# nice_n_simple_3340_v3.net
KiCad netlist of a schematic drawn in EAGLE
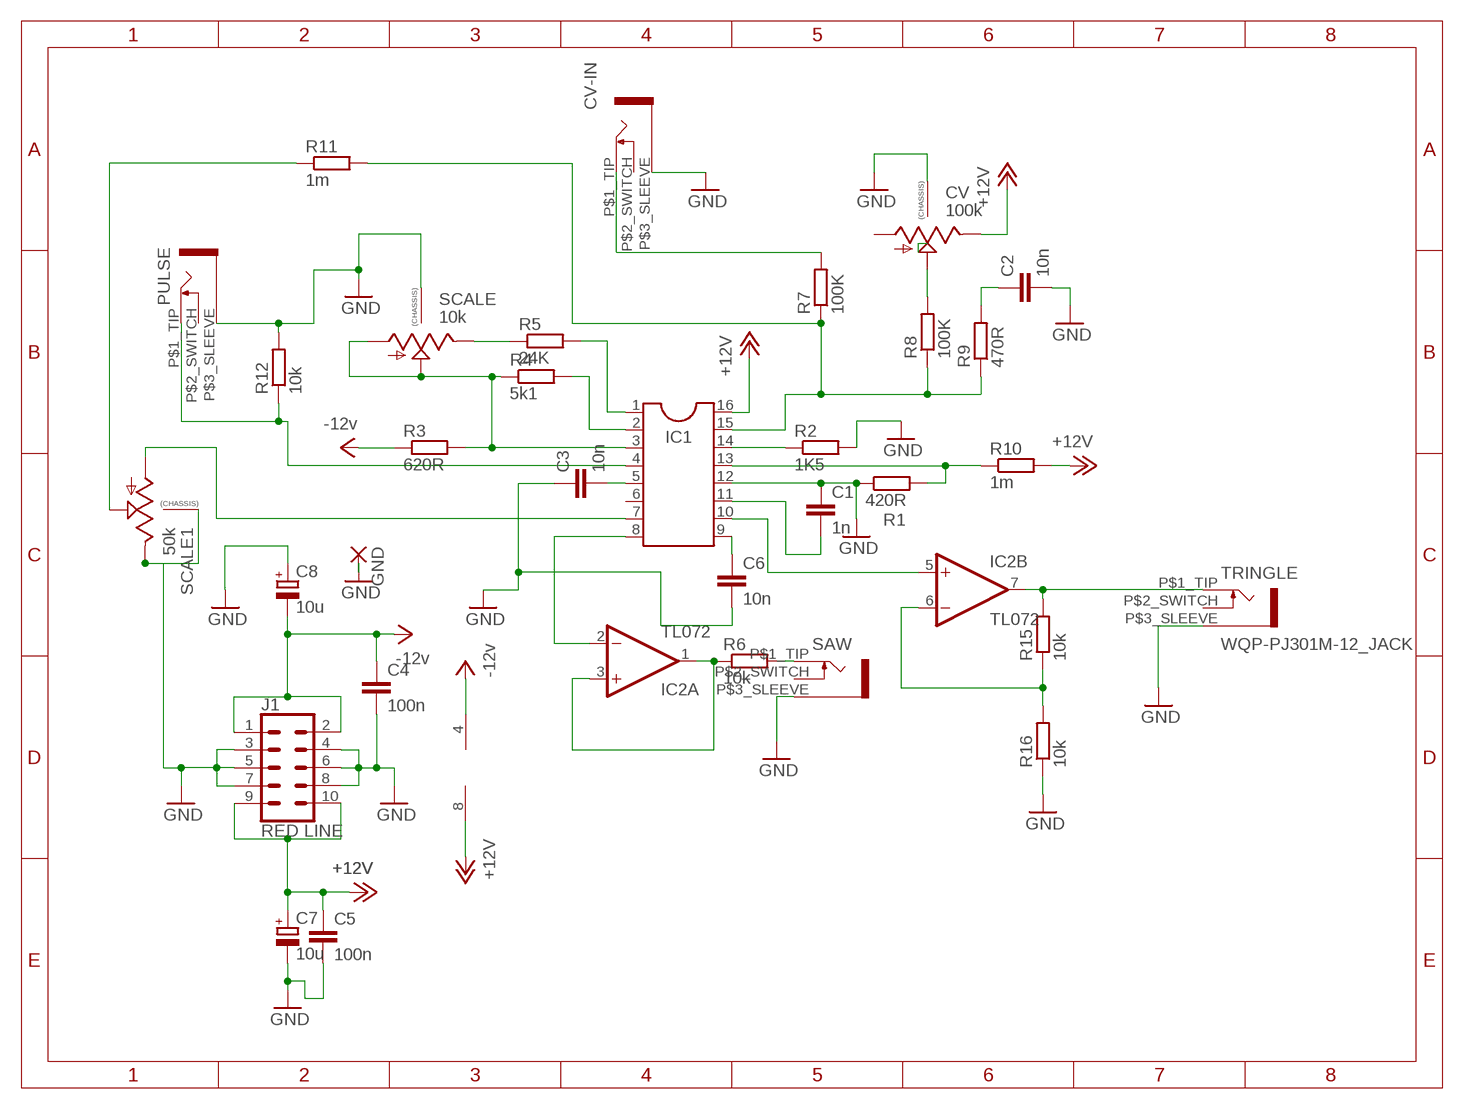
[diagram p0: schematic, sheet 1]

(export (version "E")
  (design (tool "Eeschema 10.0.6"))
  (components
    (comp (ref "C1")
      (value "1n")
      (footprint "eagle-import:C5B2.5")
      (libsource (lib "eagle-import") (part "C5/2.5"))
    )
    (comp (ref "C2")
      (value "10n")
      (footprint "eagle-import:C5B2.5")
      (libsource (lib "eagle-import") (part "C5/2.5"))
    )
    (comp (ref "C3")
      (value "10n")
      (footprint "eagle-import:C5B2.5")
      (libsource (lib "eagle-import") (part "C5/2.5"))
    )
    (comp (ref "C4")
      (value "100n")
      (footprint "eagle-import:C5B2.5")
      (libsource (lib "eagle-import") (part "C5/2.5"))
    )
    (comp (ref "C5")
      (value "100n")
      (footprint "eagle-import:C5B2.5")
      (libsource (lib "eagle-import") (part "C5/2.5"))
    )
    (comp (ref "C6")
      (value "10n")
      (footprint "eagle-import:C5B2.5")
      (libsource (lib "eagle-import") (part "C5/2.5"))
    )
    (comp (ref "C7")
      (value "10u")
      (footprint "eagle-import:E1,8-4")
      (libsource (lib "eagle-import") (part "CPOL-EUE1.8-4"))
    )
    (comp (ref "C8")
      (value "10u")
      (footprint "eagle-import:E1,8-4")
      (libsource (lib "eagle-import") (part "CPOL-EUE1.8-4"))
    )
    (comp (ref "CV")
      (value "100k")
      (footprint "eagle-import:9MM_SNAP-IN_POT")
      (libsource (lib "eagle-import") (part "9MM_SNAP-IN_POT_CHASSIS"))
    )
    (comp (ref "CV-IN")
      (value "WQP-PJ301M-12_JACK")
      (footprint "eagle-import:WQP-PJ301M-12_JACK")
      (libsource (lib "eagle-import") (part "WQP-PJ301M-12_JACK"))
    )
    (comp (ref "GND")
      (value "WIREPAD1,6/0,9")
      (footprint "eagle-import:1,6_0,9")
      (libsource (lib "eagle-import") (part "WIREPAD1,6/0,9"))
    )
    (comp (ref "IC1")
      (value "CEM3340")
      (footprint "eagle-import:SOCKET-16")
      (libsource (lib "eagle-import") (part "DIL16S"))
    )
    (comp (ref "IC2")
      (value "TL072")
      (footprint "eagle-import:DIL08")
      (libsource (lib "eagle-import") (part "TL072P"))
    )
    (comp (ref "J1")
      (value "RED LINE")
      (footprint "eagle-import:2X5-SHROUDED-NS")
      (libsource (lib "eagle-import") (part "CONN_05X2SHD-NS"))
    )
    (comp (ref "PULSE")
      (value "WQP-PJ301M-12_JACK")
      (footprint "eagle-import:WQP-PJ301M-12_JACK")
      (libsource (lib "eagle-import") (part "WQP-PJ301M-12_JACK"))
    )
    (comp (ref "R1")
      (value "420R")
      (footprint "eagle-import:0207_7")
      (libsource (lib "eagle-import") (part "R-EU_0207/7"))
    )
    (comp (ref "R2")
      (value "1K5")
      (footprint "eagle-import:0207_7")
      (libsource (lib "eagle-import") (part "R-EU_0207/7"))
    )
    (comp (ref "R3")
      (value "620R")
      (footprint "eagle-import:0207_7")
      (libsource (lib "eagle-import") (part "R-EU_0207/7"))
    )
    (comp (ref "R4")
      (value "5k1")
      (footprint "eagle-import:0207_7")
      (libsource (lib "eagle-import") (part "R-EU_0207/7"))
    )
    (comp (ref "R5")
      (value "24K")
      (footprint "eagle-import:0207_7")
      (libsource (lib "eagle-import") (part "R-EU_0207/7"))
    )
    (comp (ref "R6")
      (value "10k")
      (footprint "eagle-import:0207_7")
      (libsource (lib "eagle-import") (part "R-EU_0207/7"))
    )
    (comp (ref "R7")
      (value "100K")
      (footprint "eagle-import:0207_7")
      (libsource (lib "eagle-import") (part "R-EU_0207/7"))
    )
    (comp (ref "R8")
      (value "100K")
      (footprint "eagle-import:0207_7")
      (libsource (lib "eagle-import") (part "R-EU_0207/7"))
    )
    (comp (ref "R9")
      (value "470R")
      (footprint "eagle-import:0207_7")
      (libsource (lib "eagle-import") (part "R-EU_0207/7"))
    )
    (comp (ref "R10")
      (value "1m")
      (footprint "eagle-import:0207_7")
      (libsource (lib "eagle-import") (part "R-EU_0207/7"))
    )
    (comp (ref "R11")
      (value "1m")
      (footprint "eagle-import:0207_7")
      (libsource (lib "eagle-import") (part "R-EU_0207/7"))
    )
    (comp (ref "R12")
      (value "10k")
      (footprint "eagle-import:0207_7")
      (libsource (lib "eagle-import") (part "R-EU_0207/7"))
    )
    (comp (ref "R15")
      (value "10k")
      (footprint "eagle-import:0207_7")
      (libsource (lib "eagle-import") (part "R-EU_0207/7"))
    )
    (comp (ref "R16")
      (value "10k")
      (footprint "eagle-import:0207_7")
      (libsource (lib "eagle-import") (part "R-EU_0207/7"))
    )
    (comp (ref "SAW")
      (value "WQP-PJ301M-12_JACK")
      (footprint "eagle-import:WQP-PJ301M-12_JACK")
      (libsource (lib "eagle-import") (part "WQP-PJ301M-12_JACK"))
    )
    (comp (ref "SCALE")
      (value "10k")
      (footprint "eagle-import:9MM_SNAP-IN_POT")
      (libsource (lib "eagle-import") (part "9MM_SNAP-IN_POT_CHASSIS"))
    )
    (comp (ref "SCALE1")
      (value "50k")
      (footprint "eagle-import:9MM_SNAP-IN_POT")
      (libsource (lib "eagle-import") (part "9MM_SNAP-IN_POT_CHASSIS"))
    )
    (comp (ref "TRINGLE")
      (value "WQP-PJ301M-12_JACK")
      (footprint "eagle-import:WQP-PJ301M-12_JACK")
      (libsource (lib "eagle-import") (part "WQP-PJ301M-12_JACK"))
    )
  )
  (nets
    (net (code "1") (name "+12V") (class "Default")
      (node (ref "C5") (pin "1") (pinfunction "1_1") (pintype "passive"))
      (node (ref "C7") (pin "+") (pinfunction "+_+") (pintype "passive"))
      (node (ref "CV") (pin "3") (pinfunction "E_3") (pintype "passive"))
      (node (ref "IC1") (pin "16") (pinfunction "16_16") (pintype "passive"))
      (node (ref "IC2") (pin "8") (pinfunction "V+_8") (pintype "power_in"))
      (node (ref "J1") (pin "10") (pinfunction "10_10") (pintype "passive"))
      (node (ref "J1") (pin "9") (pinfunction "9_9") (pintype "passive"))
      (node (ref "R10") (pin "2") (pinfunction "2_2") (pintype "passive"))
    )
    (net (code "2") (name "-12v") (class "Default")
      (node (ref "C4") (pin "1") (pinfunction "1_1") (pintype "passive"))
      (node (ref "C8") (pin "-") (pinfunction "-_-") (pintype "passive"))
      (node (ref "IC2") (pin "4") (pinfunction "V-_4") (pintype "power_in"))
      (node (ref "J1") (pin "1") (pinfunction "1_1") (pintype "passive"))
      (node (ref "J1") (pin "2") (pinfunction "2_2") (pintype "passive"))
      (node (ref "R3") (pin "1") (pinfunction "1_1") (pintype "passive"))
    )
    (net (code "3") (name "GND") (class "Default")
      (node (ref "C1") (pin "1") (pinfunction "1_1") (pintype "passive"))
      (node (ref "C2") (pin "2") (pinfunction "2_2") (pintype "passive"))
      (node (ref "C3") (pin "1") (pinfunction "1_1") (pintype "passive"))
      (node (ref "C4") (pin "2") (pinfunction "2_2") (pintype "passive"))
      (node (ref "C5") (pin "2") (pinfunction "2_2") (pintype "passive"))
      (node (ref "C6") (pin "2") (pinfunction "2_2") (pintype "passive"))
      (node (ref "C7") (pin "-") (pinfunction "-_-") (pintype "passive"))
      (node (ref "C8") (pin "+") (pinfunction "+_+") (pintype "passive"))
      (node (ref "CV") (pin "CHASSIS1") (pinfunction "P$1_CHASSIS1") (pintype "passive"))
      (node (ref "CV") (pin "CHASSIS2") (pinfunction "P$1_CHASSIS2") (pintype "passive"))
      (node (ref "CV-IN") (pin "P$3_SLEEVE") (pinfunction "1_P$3_SLEEVE") (pintype "passive"))
      (node (ref "GND") (pin "1") (pinfunction "P_1") (pintype "passive"))
      (node (ref "IC1") (pin "12") (pinfunction "12_12") (pintype "passive"))
      (node (ref "J1") (pin "3") (pinfunction "3_3") (pintype "passive"))
      (node (ref "J1") (pin "4") (pinfunction "4_4") (pintype "passive"))
      (node (ref "J1") (pin "5") (pinfunction "5_5") (pintype "passive"))
      (node (ref "J1") (pin "6") (pinfunction "6_6") (pintype "passive"))
      (node (ref "J1") (pin "7") (pinfunction "7_7") (pintype "passive"))
      (node (ref "J1") (pin "8") (pinfunction "8_8") (pintype "passive"))
      (node (ref "PULSE") (pin "P$3_SLEEVE") (pinfunction "1_P$3_SLEEVE") (pintype "passive"))
      (node (ref "R1") (pin "1") (pinfunction "1_1") (pintype "passive"))
      (node (ref "R12") (pin "2") (pinfunction "2_2") (pintype "passive"))
      (node (ref "R16") (pin "1") (pinfunction "1_1") (pintype "passive"))
      (node (ref "R2") (pin "2") (pinfunction "2_2") (pintype "passive"))
      (node (ref "SAW") (pin "P$3_SLEEVE") (pinfunction "1_P$3_SLEEVE") (pintype "passive"))
      (node (ref "SCALE") (pin "CHASSIS1") (pinfunction "P$1_CHASSIS1") (pintype "passive"))
      (node (ref "SCALE") (pin "CHASSIS2") (pinfunction "P$1_CHASSIS2") (pintype "passive"))
      (node (ref "SCALE1") (pin "3") (pinfunction "E_3") (pintype "passive"))
      (node (ref "SCALE1") (pin "CHASSIS1") (pinfunction "P$1_CHASSIS1") (pintype "passive"))
      (node (ref "SCALE1") (pin "CHASSIS2") (pinfunction "P$1_CHASSIS2") (pintype "passive"))
      (node (ref "TRINGLE") (pin "P$3_SLEEVE") (pinfunction "1_P$3_SLEEVE") (pintype "passive"))
    )
    (net (code "4") (name "Net-(C1-Pad2)") (class "Default")
      (node (ref "C1") (pin "2") (pinfunction "2_2") (pintype "passive"))
      (node (ref "IC1") (pin "11") (pinfunction "11_11") (pintype "passive"))
    )
    (net (code "5") (name "Net-(C2-Pad1)") (class "Default")
      (node (ref "C2") (pin "1") (pinfunction "1_1") (pintype "passive"))
      (node (ref "R9") (pin "2") (pinfunction "2_2") (pintype "passive"))
    )
    (net (code "6") (name "Net-(C3-Pad2)") (class "Default")
      (node (ref "C3") (pin "2") (pinfunction "2_2") (pintype "passive"))
      (node (ref "IC1") (pin "5") (pinfunction "5_5") (pintype "passive"))
    )
    (net (code "7") (name "Net-(C6-Pad1)") (class "Default")
      (node (ref "C6") (pin "1") (pinfunction "1_1") (pintype "passive"))
      (node (ref "IC1") (pin "9") (pinfunction "9_9") (pintype "passive"))
    )
    (net (code "8") (name "Net-(CV-IN-2)") (class "Default")
      (node (ref "CV-IN") (pin "P$1_TIP") (pinfunction "2_P$1_TIP") (pintype "passive"))
      (node (ref "R7") (pin "2") (pinfunction "2_2") (pintype "passive"))
    )
    (net (code "9") (name "Net-(CV-S)") (class "Default")
      (node (ref "CV") (pin "2") (pinfunction "S_2") (pintype "passive"))
      (node (ref "R8") (pin "2") (pinfunction "2_2") (pintype "passive"))
    )
    (net (code "10") (name "Net-(IC1-Pad1)") (class "Default")
      (node (ref "IC1") (pin "1") (pinfunction "1_1") (pintype "passive"))
      (node (ref "R5") (pin "2") (pinfunction "2_2") (pintype "passive"))
    )
    (net (code "11") (name "Net-(IC1-Pad2)") (class "Default")
      (node (ref "IC1") (pin "2") (pinfunction "2_2") (pintype "passive"))
      (node (ref "R4") (pin "2") (pinfunction "2_2") (pintype "passive"))
    )
    (net (code "12") (name "Net-(IC1-Pad13)") (class "Default")
      (node (ref "IC1") (pin "13") (pinfunction "13_13") (pintype "passive"))
      (node (ref "R1") (pin "2") (pinfunction "2_2") (pintype "passive"))
      (node (ref "R10") (pin "1") (pinfunction "1_1") (pintype "passive"))
    )
    (net (code "13") (name "Net-(IC1-Pad14)") (class "Default")
      (node (ref "IC1") (pin "14") (pinfunction "14_14") (pintype "passive"))
      (node (ref "R2") (pin "1") (pinfunction "1_1") (pintype "passive"))
    )
    (net (code "14") (name "Net-(IC1-Pad15)") (class "Default")
      (node (ref "IC1") (pin "15") (pinfunction "15_15") (pintype "passive"))
      (node (ref "R11") (pin "2") (pinfunction "2_2") (pintype "passive"))
      (node (ref "R7") (pin "1") (pinfunction "1_1") (pintype "passive"))
      (node (ref "R8") (pin "1") (pinfunction "1_1") (pintype "passive"))
      (node (ref "R9") (pin "1") (pinfunction "1_1") (pintype "passive"))
    )
    (net (code "15") (name "Net-(IC2A-+IN)") (class "Default")
      (node (ref "IC2") (pin "1") (pinfunction "OUT_1") (pintype "output"))
      (node (ref "IC2") (pin "3") (pinfunction "+IN_3") (pintype "input"))
      (node (ref "R6") (pin "1") (pinfunction "1_1") (pintype "passive"))
    )
    (net (code "16") (name "Net-(IC2A--IN)") (class "Default")
      (node (ref "IC1") (pin "8") (pinfunction "8_8") (pintype "passive"))
      (node (ref "IC2") (pin "2") (pinfunction "-IN_2") (pintype "input"))
    )
    (net (code "17") (name "Net-(IC2B-+IN)") (class "Default")
      (node (ref "IC1") (pin "10") (pinfunction "10_10") (pintype "passive"))
      (node (ref "IC2") (pin "5") (pinfunction "+IN_5") (pintype "input"))
    )
    (net (code "18") (name "Net-(IC2B--IN)") (class "Default")
      (node (ref "IC2") (pin "6") (pinfunction "-IN_6") (pintype "input"))
      (node (ref "R15") (pin "1") (pinfunction "1_1") (pintype "passive"))
      (node (ref "R16") (pin "2") (pinfunction "2_2") (pintype "passive"))
    )
    (net (code "19") (name "Net-(IC2B-OUT)") (class "Default")
      (node (ref "IC2") (pin "7") (pinfunction "OUT_7") (pintype "output"))
      (node (ref "R15") (pin "2") (pinfunction "2_2") (pintype "passive"))
      (node (ref "TRINGLE") (pin "P$1_TIP") (pinfunction "2_P$1_TIP") (pintype "passive"))
    )
    (net (code "20") (name "Net-(PULSE-2)") (class "Default")
      (node (ref "IC1") (pin "4") (pinfunction "4_4") (pintype "passive"))
      (node (ref "PULSE") (pin "P$1_TIP") (pinfunction "2_P$1_TIP") (pintype "passive"))
      (node (ref "R12") (pin "1") (pinfunction "1_1") (pintype "passive"))
    )
    (net (code "21") (name "Net-(SAW-2)") (class "Default")
      (node (ref "R6") (pin "2") (pinfunction "2_2") (pintype "passive"))
      (node (ref "SAW") (pin "P$1_TIP") (pinfunction "2_P$1_TIP") (pintype "passive"))
    )
    (net (code "22") (name "Net-(SCALE-A)") (class "Default")
      (node (ref "IC1") (pin "3") (pinfunction "3_3") (pintype "passive"))
      (node (ref "R3") (pin "2") (pinfunction "2_2") (pintype "passive"))
      (node (ref "R4") (pin "1") (pinfunction "1_1") (pintype "passive"))
      (node (ref "SCALE") (pin "1") (pinfunction "A_1") (pintype "passive"))
      (node (ref "SCALE") (pin "2") (pinfunction "S_2") (pintype "passive"))
    )
    (net (code "23") (name "Net-(SCALE-E)") (class "Default")
      (node (ref "R5") (pin "1") (pinfunction "1_1") (pintype "passive"))
      (node (ref "SCALE") (pin "3") (pinfunction "E_3") (pintype "passive"))
    )
    (net (code "24") (name "Net-(SCALE1-A)") (class "Default")
      (node (ref "IC1") (pin "7") (pinfunction "7_7") (pintype "passive"))
      (node (ref "SCALE1") (pin "1") (pinfunction "A_1") (pintype "passive"))
    )
    (net (code "25") (name "Net-(SCALE1-S)") (class "Default")
      (node (ref "R11") (pin "1") (pinfunction "1_1") (pintype "passive"))
      (node (ref "SCALE1") (pin "2") (pinfunction "S_2") (pintype "passive"))
    )
    (net (code "26") (name "unconnected-(CV-A-Pad1)") (class "Default")
      (node (ref "CV") (pin "1") (pinfunction "A_1") (pintype "passive"))
    )
    (net (code "27") (name "unconnected-(CV-IN-3-PadP$2_SWITCH)") (class "Default")
      (node (ref "CV-IN") (pin "P$2_SWITCH") (pinfunction "3_P$2_SWITCH") (pintype "passive"))
    )
    (net (code "28") (name "unconnected-(IC1-Pad6)") (class "Default")
      (node (ref "IC1") (pin "6") (pinfunction "6_6") (pintype "passive"))
    )
    (net (code "29") (name "unconnected-(PULSE-3-PadP$2_SWITCH)") (class "Default")
      (node (ref "PULSE") (pin "P$2_SWITCH") (pinfunction "3_P$2_SWITCH") (pintype "passive"))
    )
    (net (code "30") (name "unconnected-(SAW-3-PadP$2_SWITCH)") (class "Default")
      (node (ref "SAW") (pin "P$2_SWITCH") (pinfunction "3_P$2_SWITCH") (pintype "passive"))
    )
    (net (code "31") (name "unconnected-(TRINGLE-3-PadP$2_SWITCH)") (class "Default")
      (node (ref "TRINGLE") (pin "P$2_SWITCH") (pinfunction "3_P$2_SWITCH") (pintype "passive"))
    )
  )
)
